# IO_Peripherals.net
KiCad netlist of a schematic drawn in Altium Designer
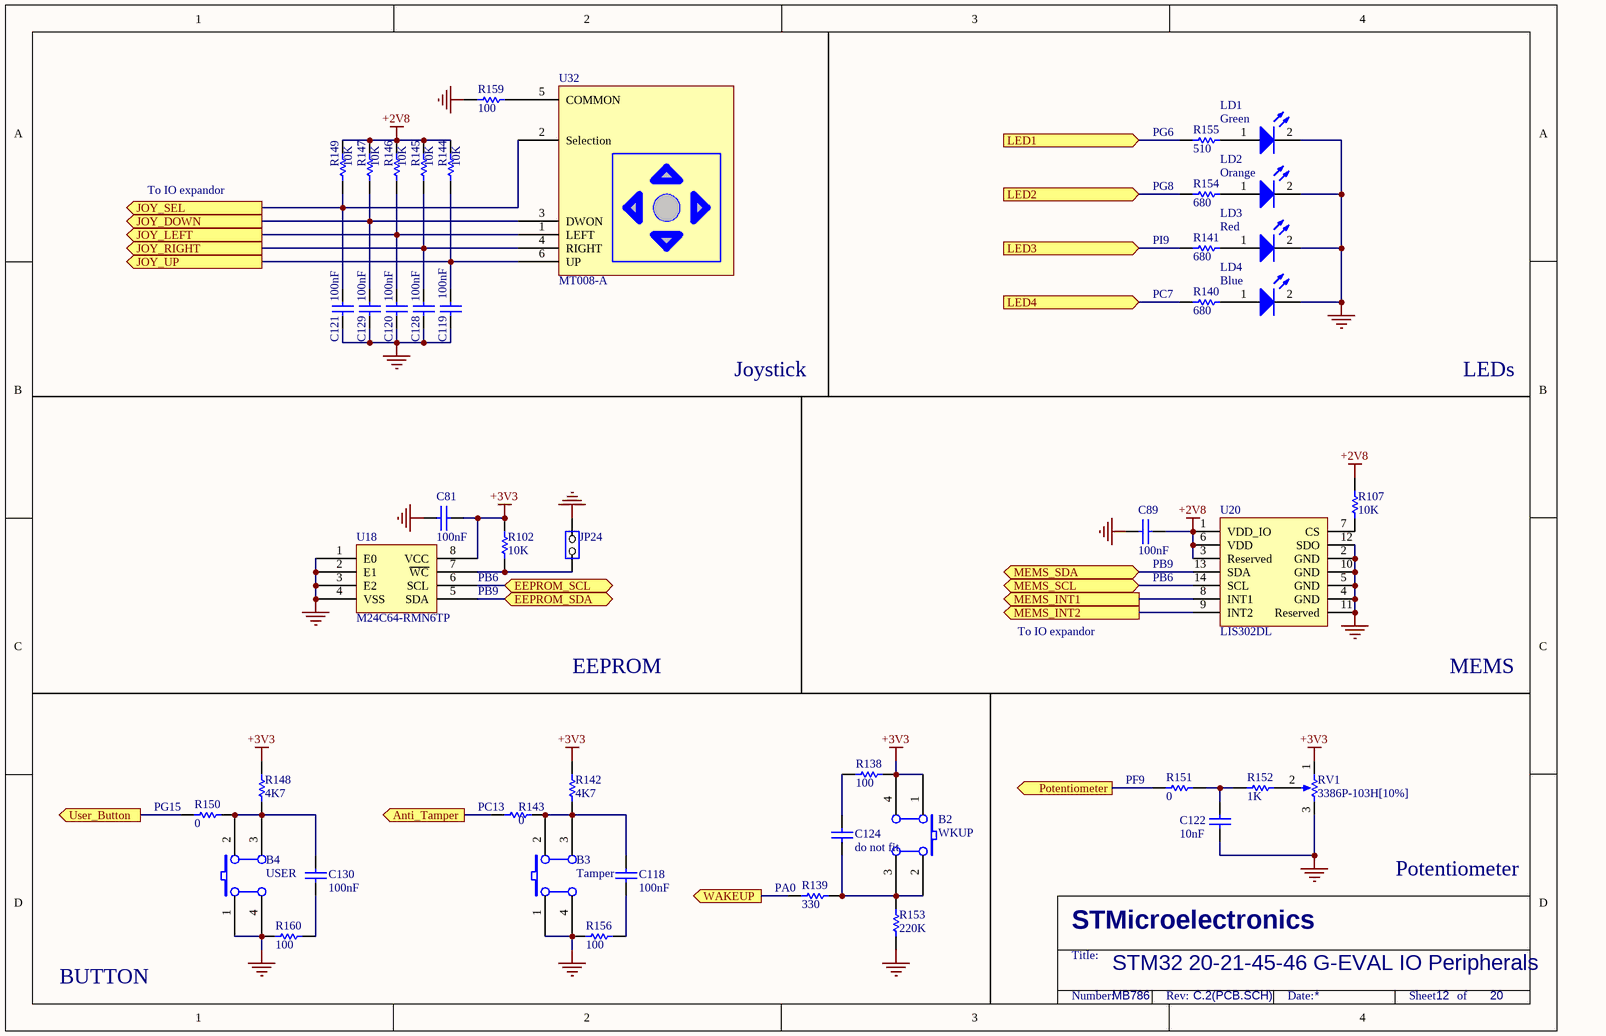
[diagram p0: IO Peripherals.SchDoc]

(export (version "E")
  (design (tool "Eeschema 10.0.6"))
  (components
    (comp (ref "B2")
      (value "WKUP")
      (footprint "PB10")
      (description "SE PUSHBUTTON")
      (libsource (lib "Documents") (part "SW PUSHBUTTON"))
    )
    (comp (ref "B3")
      (value "Tamper")
      (footprint "PB10")
      (description "SE PUSHBUTTON")
      (libsource (lib "Documents") (part "SW PUSHBUTTON"))
    )
    (comp (ref "B4")
      (value "USER")
      (footprint "PB10")
      (description "SE PUSHBUTTON")
      (libsource (lib "Documents") (part "SW PUSHBUTTON"))
    )
    (comp (ref "C81")
      (value "100nF")
      (footprint "0402C")
      (description "Capacitor")
      (libsource (lib "*") (part "CAP"))
    )
    (comp (ref "C89")
      (value "100nF")
      (footprint "0402C")
      (description "Capacitor")
      (libsource (lib "*") (part "CAP"))
    )
    (comp (ref "C118")
      (value "100nF")
      (footprint "0402C")
      (description "Capacitor")
      (fields (field (name "PUBLISHER") "Altium Limited"))
      (libsource (lib "Miscellaneous Devices") (part "CAP"))
    )
    (comp (ref "C119")
      (value "100nF")
      (footprint "0402C")
      (description "Capacitor")
      (fields (field (name "PUBLISHER") "Altium Limited"))
      (libsource (lib "Miscellaneous Devices") (part "CAP"))
    )
    (comp (ref "C120")
      (value "100nF")
      (footprint "0402C")
      (description "Capacitor")
      (fields (field (name "PUBLISHER") "Altium Limited"))
      (libsource (lib "Miscellaneous Devices") (part "CAP"))
    )
    (comp (ref "C121")
      (value "100nF")
      (footprint "0402C")
      (description "Capacitor")
      (fields (field (name "PUBLISHER") "Altium Limited"))
      (libsource (lib "Miscellaneous Devices") (part "CAP"))
    )
    (comp (ref "C122")
      (value "10nF")
      (footprint "0402C")
      (description "Capacitor")
      (fields (field (name "PUBLISHER") "Altium Limited"))
      (libsource (lib "Miscellaneous Devices") (part "CAP"))
    )
    (comp (ref "C124")
      (value "do not fit")
      (footprint "0603C")
      (description "Capacitor")
      (fields (field (name "PUBLISHER") "Altium Limited"))
      (libsource (lib "Miscellaneous Devices") (part "CAP"))
    )
    (comp (ref "C128")
      (value "100nF")
      (footprint "0402C")
      (description "Capacitor")
      (fields (field (name "PUBLISHER") "Altium Limited"))
      (libsource (lib "Miscellaneous Devices") (part "CAP"))
    )
    (comp (ref "C129")
      (value "100nF")
      (footprint "0402C")
      (description "Capacitor")
      (fields (field (name "PUBLISHER") "Altium Limited"))
      (libsource (lib "Miscellaneous Devices") (part "CAP"))
    )
    (comp (ref "C130")
      (value "100nF")
      (footprint "0402C")
      (description "Capacitor")
      (fields (field (name "PUBLISHER") "Altium Limited"))
      (libsource (lib "Miscellaneous Devices") (part "CAP"))
    )
    (comp (ref "JP24") (value "~") (footprint "SIP2") (libsource (lib "*") (part "JP2")))
    (comp (ref "LD1")
      (value "Green")
      (footprint "0603D")
      (description "Typical RED, GREEN, YELLOW, AMBER GaAs LED")
      (fields (field (name "PUBLISHER") "Altium Limited"))
      (libsource (lib "Miscellaneous Devices") (part "LED2"))
    )
    (comp (ref "LD2")
      (value "Orange")
      (footprint "0603D")
      (description "Typical RED, GREEN, YELLOW, AMBER GaAs LED")
      (fields (field (name "PUBLISHER") "Altium Limited"))
      (libsource (lib "Miscellaneous Devices") (part "LED2"))
    )
    (comp (ref "LD3")
      (value "Red")
      (footprint "0603D")
      (description "Typical RED, GREEN, YELLOW, AMBER GaAs LED")
      (fields (field (name "PUBLISHER") "Altium Limited"))
      (libsource (lib "Miscellaneous Devices") (part "LED2"))
    )
    (comp (ref "LD4")
      (value "Blue")
      (footprint "0603D")
      (description "Typical RED, GREEN, YELLOW, AMBER GaAs LED")
      (fields (field (name "PUBLISHER") "Altium Limited"))
      (libsource (lib "Miscellaneous Devices") (part "LED2"))
    )
    (comp (ref "R102")
      (value "10K")
      (footprint "0402R")
      (description "Resistor")
      (fields (field (name "PUBLISHER") "Altium Limited"))
      (libsource (lib "Miscellaneous Devices") (part "res1"))
    )
    (comp (ref "R107")
      (value "10K")
      (footprint "0402R")
      (description "Resistor")
      (fields (field (name "PUBLISHER") "Altium Limited"))
      (libsource (lib "Miscellaneous Devices") (part "res1"))
    )
    (comp (ref "R138")
      (value "100")
      (footprint "0603R")
      (description "Resistor")
      (fields (field (name "PUBLISHER") "Altium Limited"))
      (libsource (lib "Miscellaneous Devices") (part "Res1"))
    )
    (comp (ref "R139")
      (value "330")
      (footprint "0603R")
      (description "Resistor")
      (fields (field (name "PUBLISHER") "Altium Limited"))
      (libsource (lib "Miscellaneous Devices") (part "Res1"))
    )
    (comp (ref "R140")
      (value "680")
      (footprint "0603R")
      (description "Resistor")
      (fields (field (name "PUBLISHER") "Altium Limited"))
      (libsource (lib "Miscellaneous Devices") (part "Res1"))
    )
    (comp (ref "R141")
      (value "680")
      (footprint "0603R")
      (description "Resistor")
      (fields (field (name "PUBLISHER") "Altium Limited"))
      (libsource (lib "Miscellaneous Devices") (part "Res1"))
    )
    (comp (ref "R142")
      (value "4K7")
      (footprint "0402R")
      (description "Resistor")
      (fields (field (name "PUBLISHER") "Altium Limited"))
      (libsource (lib "Miscellaneous Devices") (part "res1"))
    )
    (comp (ref "R143")
      (value "0")
      (footprint "0603R")
      (description "Resistor")
      (fields (field (name "PUBLISHER") "Altium Limited"))
      (libsource (lib "Miscellaneous Devices") (part "Res1"))
    )
    (comp (ref "R144")
      (value "10K")
      (footprint "0402R")
      (description "Resistor")
      (fields (field (name "PUBLISHER") "Altium Limited"))
      (libsource (lib "Miscellaneous Devices") (part "Res1"))
    )
    (comp (ref "R145")
      (value "10K")
      (footprint "0402R")
      (description "Resistor")
      (fields (field (name "PUBLISHER") "Altium Limited"))
      (libsource (lib "Miscellaneous Devices") (part "Res1"))
    )
    (comp (ref "R146")
      (value "10K")
      (footprint "0402R")
      (description "Resistor")
      (fields (field (name "PUBLISHER") "Altium Limited"))
      (libsource (lib "Miscellaneous Devices") (part "Res1"))
    )
    (comp (ref "R147")
      (value "10K")
      (footprint "0402R")
      (description "Resistor")
      (fields (field (name "PUBLISHER") "Altium Limited"))
      (libsource (lib "Miscellaneous Devices") (part "Res1"))
    )
    (comp (ref "R148")
      (value "4K7")
      (footprint "0402R")
      (description "Resistor")
      (fields (field (name "PUBLISHER") "Altium Limited"))
      (libsource (lib "Miscellaneous Devices") (part "res1"))
    )
    (comp (ref "R149")
      (value "10K")
      (footprint "0402R")
      (description "Resistor")
      (fields (field (name "PUBLISHER") "Altium Limited"))
      (libsource (lib "Miscellaneous Devices") (part "Res1"))
    )
    (comp (ref "R150")
      (value "0")
      (footprint "0603R")
      (description "Resistor")
      (fields (field (name "PUBLISHER") "Altium Limited"))
      (libsource (lib "Miscellaneous Devices") (part "Res1"))
    )
    (comp (ref "R151")
      (value "0")
      (footprint "0603R")
      (description "Resistor")
      (fields (field (name "PUBLISHER") "Altium Limited"))
      (libsource (lib "Miscellaneous Devices") (part "Res1"))
    )
    (comp (ref "R152")
      (value "1K")
      (footprint "0603R")
      (description "Resistor")
      (fields (field (name "PUBLISHER") "Altium Limited"))
      (libsource (lib "Miscellaneous Devices") (part "Res1"))
    )
    (comp (ref "R153")
      (value "220K")
      (footprint "0603R")
      (description "Resistor")
      (fields (field (name "PUBLISHER") "Altium Limited"))
      (libsource (lib "Miscellaneous Devices") (part "res1"))
    )
    (comp (ref "R154")
      (value "680")
      (footprint "0603R")
      (description "Resistor")
      (fields (field (name "PUBLISHER") "Altium Limited"))
      (libsource (lib "Miscellaneous Devices") (part "Res1"))
    )
    (comp (ref "R155")
      (value "510")
      (footprint "0603R")
      (description "Resistor")
      (fields (field (name "PUBLISHER") "Altium Limited"))
      (libsource (lib "Miscellaneous Devices") (part "Res1"))
    )
    (comp (ref "R156")
      (value "100")
      (footprint "0603R")
      (description "Resistor")
      (fields (field (name "PUBLISHER") "Altium Limited"))
      (libsource (lib "Miscellaneous Devices") (part "Res1"))
    )
    (comp (ref "R159")
      (value "100")
      (footprint "0603R")
      (description "Resistor")
      (fields (field (name "PUBLISHER") "Altium Limited"))
      (libsource (lib "Miscellaneous Devices") (part "Res1"))
    )
    (comp (ref "R160")
      (value "100")
      (footprint "0603R")
      (description "Resistor")
      (fields (field (name "PUBLISHER") "Altium Limited"))
      (libsource (lib "Miscellaneous Devices") (part "Res1"))
    )
    (comp (ref "RV1")
      (value "3386P-103H[10%]")
      (footprint "3296W")
      (libsource (lib "STR910_SCHLIB") (part "RV"))
    )
    (comp (ref "U18")
      (value "M24C64-RMN6TP")
      (footprint "SO8")
      (libsource (lib "ST79F5xx-EVAL") (part "M24C64-WMN6"))
    )
    (comp (ref "U20") (value "LIS302DL") (footprint "LGA14(3*5)") (libsource (lib "MB784") (part "LIS302DL")))
    (comp (ref "U32") (value "MT008-A") (footprint "JOY") (libsource (lib "MB513") (part "MT-008A")))
  )
  (nets
    (net (code "1") (name "+2V8") (class "Default")
      (node (ref "C89") (pin "2") (pinfunction "2_2") (pintype "passive"))
      (node (ref "R107") (pin "1") (pinfunction "1_1") (pintype "passive"))
      (node (ref "R144") (pin "2") (pinfunction "2_2") (pintype "passive"))
      (node (ref "R145") (pin "2") (pinfunction "2_2") (pintype "passive"))
      (node (ref "R146") (pin "2") (pinfunction "2_2") (pintype "passive"))
      (node (ref "R147") (pin "2") (pinfunction "2_2") (pintype "passive"))
      (node (ref "R149") (pin "1") (pinfunction "1_1") (pintype "passive"))
      (node (ref "U20") (pin "1") (pinfunction "VDD_IO_1") (pintype "passive"))
      (node (ref "U20") (pin "3") (pinfunction "Reserved_3") (pintype "passive"))
      (node (ref "U20") (pin "6") (pinfunction "VDD_6") (pintype "passive"))
    )
    (net (code "2") (name "+3V3") (class "Default")
      (node (ref "B2") (pin "1") (pinfunction "A0_1") (pintype "passive"))
      (node (ref "B2") (pin "4") (pinfunction "A1_4") (pintype "passive"))
      (node (ref "C81") (pin "2") (pinfunction "2_2") (pintype "passive"))
      (node (ref "R102") (pin "1") (pinfunction "1_1") (pintype "passive"))
      (node (ref "R138") (pin "1") (pinfunction "1_1") (pintype "passive"))
      (node (ref "R142") (pin "2") (pinfunction "2_2") (pintype "passive"))
      (node (ref "R148") (pin "2") (pinfunction "2_2") (pintype "passive"))
      (node (ref "RV1") (pin "1") (pinfunction "TOP_1") (pintype "passive"))
      (node (ref "U18") (pin "8") (pinfunction "VCC_8") (pintype "passive"))
    )
    (net (code "3") (name "/Anti_Tamper") (class "Default")
      (node (ref "R143") (pin "2") (pinfunction "2_2") (pintype "passive"))
    )
    (net (code "4") (name "/EEPROM_SCL") (class "Default")
      (node (ref "U18") (pin "6") (pinfunction "SCL_6") (pintype "passive"))
    )
    (net (code "5") (name "/EEPROM_SDA") (class "Default")
      (node (ref "U18") (pin "5") (pinfunction "SDA_5") (pintype "passive"))
    )
    (net (code "6") (name "/JOY_DOWN") (class "Default")
      (node (ref "C129") (pin "2") (pinfunction "2_2") (pintype "passive"))
      (node (ref "R147") (pin "1") (pinfunction "1_1") (pintype "passive"))
      (node (ref "U32") (pin "3") (pinfunction "DWON_3") (pintype "passive"))
    )
    (net (code "7") (name "/JOY_LEFT") (class "Default")
      (node (ref "C120") (pin "2") (pinfunction "2_2") (pintype "passive"))
      (node (ref "R146") (pin "1") (pinfunction "1_1") (pintype "passive"))
      (node (ref "U32") (pin "1") (pinfunction "LEFT_1") (pintype "passive"))
    )
    (net (code "8") (name "/JOY_RIGHT") (class "Default")
      (node (ref "C128") (pin "2") (pinfunction "2_2") (pintype "passive"))
      (node (ref "R145") (pin "1") (pinfunction "1_1") (pintype "passive"))
      (node (ref "U32") (pin "4") (pinfunction "RIGHT_4") (pintype "passive"))
    )
    (net (code "9") (name "/JOY_SEL") (class "Default")
      (node (ref "C121") (pin "2") (pinfunction "2_2") (pintype "passive"))
      (node (ref "R149") (pin "2") (pinfunction "2_2") (pintype "passive"))
      (node (ref "U32") (pin "2") (pinfunction "Selection_2") (pintype "passive"))
    )
    (net (code "10") (name "/JOY_UP") (class "Default")
      (node (ref "C119") (pin "2") (pinfunction "2_2") (pintype "passive"))
      (node (ref "R144") (pin "1") (pinfunction "1_1") (pintype "passive"))
      (node (ref "U32") (pin "6") (pinfunction "UP_6") (pintype "passive"))
    )
    (net (code "11") (name "/LED1") (class "Default")
      (node (ref "R155") (pin "2") (pinfunction "2_2") (pintype "passive"))
    )
    (net (code "12") (name "/LED2") (class "Default")
      (node (ref "R154") (pin "2") (pinfunction "2_2") (pintype "passive"))
    )
    (net (code "13") (name "/LED3") (class "Default")
      (node (ref "R141") (pin "2") (pinfunction "2_2") (pintype "passive"))
    )
    (net (code "14") (name "/LED4") (class "Default")
      (node (ref "R140") (pin "2") (pinfunction "2_2") (pintype "passive"))
    )
    (net (code "15") (name "/MEMS_INT1") (class "Default")
      (node (ref "U20") (pin "8") (pinfunction "INT1_8") (pintype "passive"))
    )
    (net (code "16") (name "/MEMS_INT2") (class "Default")
      (node (ref "U20") (pin "9") (pinfunction "INT2_9") (pintype "passive"))
    )
    (net (code "17") (name "/MEMS_SCL") (class "Default")
      (node (ref "U20") (pin "14") (pinfunction "SCL_14") (pintype "passive"))
    )
    (net (code "18") (name "/MEMS_SDA") (class "Default")
      (node (ref "U20") (pin "13") (pinfunction "SDA_13") (pintype "passive"))
    )
    (net (code "19") (name "/Potentiometer") (class "Default")
      (node (ref "R151") (pin "1") (pinfunction "1_1") (pintype "passive"))
    )
    (net (code "20") (name "/User_Button") (class "Default")
      (node (ref "R150") (pin "2") (pinfunction "2_2") (pintype "passive"))
    )
    (net (code "21") (name "/WAKEUP") (class "Default")
      (node (ref "R139") (pin "2") (pinfunction "2_2") (pintype "passive"))
    )
    (net (code "22") (name "GND") (class "Default")
      (node (ref "B3") (pin "1") (pinfunction "A0_1") (pintype "passive"))
      (node (ref "B3") (pin "4") (pinfunction "A1_4") (pintype "passive"))
      (node (ref "B4") (pin "1") (pinfunction "A0_1") (pintype "passive"))
      (node (ref "B4") (pin "4") (pinfunction "A1_4") (pintype "passive"))
      (node (ref "C119") (pin "1") (pinfunction "1_1") (pintype "passive"))
      (node (ref "C120") (pin "1") (pinfunction "1_1") (pintype "passive"))
      (node (ref "C121") (pin "1") (pinfunction "1_1") (pintype "passive"))
      (node (ref "C122") (pin "1") (pinfunction "1_1") (pintype "passive"))
      (node (ref "C128") (pin "1") (pinfunction "1_1") (pintype "passive"))
      (node (ref "C129") (pin "1") (pinfunction "1_1") (pintype "passive"))
      (node (ref "C81") (pin "1") (pinfunction "1_1") (pintype "passive"))
      (node (ref "C89") (pin "1") (pinfunction "1_1") (pintype "passive"))
      (node (ref "JP24") (pin "2") (pinfunction "NO_2") (pintype "passive"))
      (node (ref "LD1") (pin "2") (pinfunction "K_2") (pintype "passive"))
      (node (ref "LD2") (pin "2") (pinfunction "K_2") (pintype "passive"))
      (node (ref "LD3") (pin "2") (pinfunction "K_2") (pintype "passive"))
      (node (ref "LD4") (pin "2") (pinfunction "K_2") (pintype "passive"))
      (node (ref "R153") (pin "2") (pinfunction "2_2") (pintype "passive"))
      (node (ref "R156") (pin "1") (pinfunction "1_1") (pintype "passive"))
      (node (ref "R159") (pin "1") (pinfunction "1_1") (pintype "passive"))
      (node (ref "R160") (pin "1") (pinfunction "1_1") (pintype "passive"))
      (node (ref "RV1") (pin "3") (pinfunction "BOT_3") (pintype "passive"))
      (node (ref "U18") (pin "1") (pinfunction "E0_1") (pintype "passive"))
      (node (ref "U18") (pin "2") (pinfunction "E1_2") (pintype "passive"))
      (node (ref "U18") (pin "3") (pinfunction "E2_3") (pintype "passive"))
      (node (ref "U18") (pin "4") (pinfunction "VSS_4") (pintype "passive"))
      (node (ref "U20") (pin "10") (pinfunction "GND_10") (pintype "passive"))
      (node (ref "U20") (pin "11") (pinfunction "Reserved_11") (pintype "passive"))
      (node (ref "U20") (pin "12") (pinfunction "SDO_12") (pintype "passive"))
      (node (ref "U20") (pin "2") (pinfunction "GND_2") (pintype "passive"))
      (node (ref "U20") (pin "4") (pinfunction "GND_4") (pintype "passive"))
      (node (ref "U20") (pin "5") (pinfunction "GND_5") (pintype "passive"))
    )
    (net (code "23") (name "Net-(B2-B0)") (class "Default")
      (node (ref "B2") (pin "2") (pinfunction "B0_2") (pintype "passive"))
      (node (ref "B2") (pin "3") (pinfunction "B1_3") (pintype "passive"))
      (node (ref "C124") (pin "2") (pinfunction "2_2") (pintype "passive"))
      (node (ref "R139") (pin "1") (pinfunction "1_1") (pintype "passive"))
      (node (ref "R153") (pin "1") (pinfunction "1_1") (pintype "passive"))
    )
    (net (code "24") (name "Net-(B3-B0)") (class "Default")
      (node (ref "B3") (pin "2") (pinfunction "B0_2") (pintype "passive"))
      (node (ref "B3") (pin "3") (pinfunction "B1_3") (pintype "passive"))
      (node (ref "C118") (pin "2") (pinfunction "2_2") (pintype "passive"))
      (node (ref "R142") (pin "1") (pinfunction "1_1") (pintype "passive"))
      (node (ref "R143") (pin "1") (pinfunction "1_1") (pintype "passive"))
    )
    (net (code "25") (name "Net-(B4-B0)") (class "Default")
      (node (ref "B4") (pin "2") (pinfunction "B0_2") (pintype "passive"))
      (node (ref "B4") (pin "3") (pinfunction "B1_3") (pintype "passive"))
      (node (ref "C130") (pin "2") (pinfunction "2_2") (pintype "passive"))
      (node (ref "R148") (pin "1") (pinfunction "1_1") (pintype "passive"))
      (node (ref "R150") (pin "1") (pinfunction "1_1") (pintype "passive"))
    )
    (net (code "26") (name "Net-(C118-Pad1)") (class "Default")
      (node (ref "C118") (pin "1") (pinfunction "1_1") (pintype "passive"))
      (node (ref "R156") (pin "2") (pinfunction "2_2") (pintype "passive"))
    )
    (net (code "27") (name "Net-(C122-Pad2)") (class "Default")
      (node (ref "C122") (pin "2") (pinfunction "2_2") (pintype "passive"))
      (node (ref "R151") (pin "2") (pinfunction "2_2") (pintype "passive"))
      (node (ref "R152") (pin "1") (pinfunction "1_1") (pintype "passive"))
    )
    (net (code "28") (name "Net-(C124-Pad1)") (class "Default")
      (node (ref "C124") (pin "1") (pinfunction "1_1") (pintype "passive"))
      (node (ref "R138") (pin "2") (pinfunction "2_2") (pintype "passive"))
    )
    (net (code "29") (name "Net-(C130-Pad1)") (class "Default")
      (node (ref "C130") (pin "1") (pinfunction "1_1") (pintype "passive"))
      (node (ref "R160") (pin "2") (pinfunction "2_2") (pintype "passive"))
    )
    (net (code "30") (name "Net-(JP24-COMMON)") (class "Default")
      (node (ref "JP24") (pin "1") (pinfunction "COMMON_1") (pintype "passive"))
      (node (ref "R102") (pin "2") (pinfunction "2_2") (pintype "passive"))
      (node (ref "U18") (pin "7") (pinfunction "~{WC}_7") (pintype "passive"))
    )
    (net (code "31") (name "Net-(LD1-A)") (class "Default")
      (node (ref "LD1") (pin "1") (pinfunction "A_1") (pintype "passive"))
      (node (ref "R155") (pin "1") (pinfunction "1_1") (pintype "passive"))
    )
    (net (code "32") (name "Net-(LD2-A)") (class "Default")
      (node (ref "LD2") (pin "1") (pinfunction "A_1") (pintype "passive"))
      (node (ref "R154") (pin "1") (pinfunction "1_1") (pintype "passive"))
    )
    (net (code "33") (name "Net-(LD3-A)") (class "Default")
      (node (ref "LD3") (pin "1") (pinfunction "A_1") (pintype "passive"))
      (node (ref "R141") (pin "1") (pinfunction "1_1") (pintype "passive"))
    )
    (net (code "34") (name "Net-(LD4-A)") (class "Default")
      (node (ref "LD4") (pin "1") (pinfunction "A_1") (pintype "passive"))
      (node (ref "R140") (pin "1") (pinfunction "1_1") (pintype "passive"))
    )
    (net (code "35") (name "Net-(RV1-TAP)") (class "Default")
      (node (ref "R152") (pin "2") (pinfunction "2_2") (pintype "passive"))
      (node (ref "RV1") (pin "2") (pinfunction "TAP_2") (pintype "passive"))
    )
    (net (code "36") (name "Net-(U20-CS)") (class "Default")
      (node (ref "R107") (pin "2") (pinfunction "2_2") (pintype "passive"))
      (node (ref "U20") (pin "7") (pinfunction "CS_7") (pintype "passive"))
    )
    (net (code "37") (name "Net-(U32-COMMON)") (class "Default")
      (node (ref "R159") (pin "2") (pinfunction "2_2") (pintype "passive"))
      (node (ref "U32") (pin "5") (pinfunction "COMMON_5") (pintype "passive"))
    )
  )
)
